# CONN.net
KiCad netlist of a schematic drawn in Altium Designer
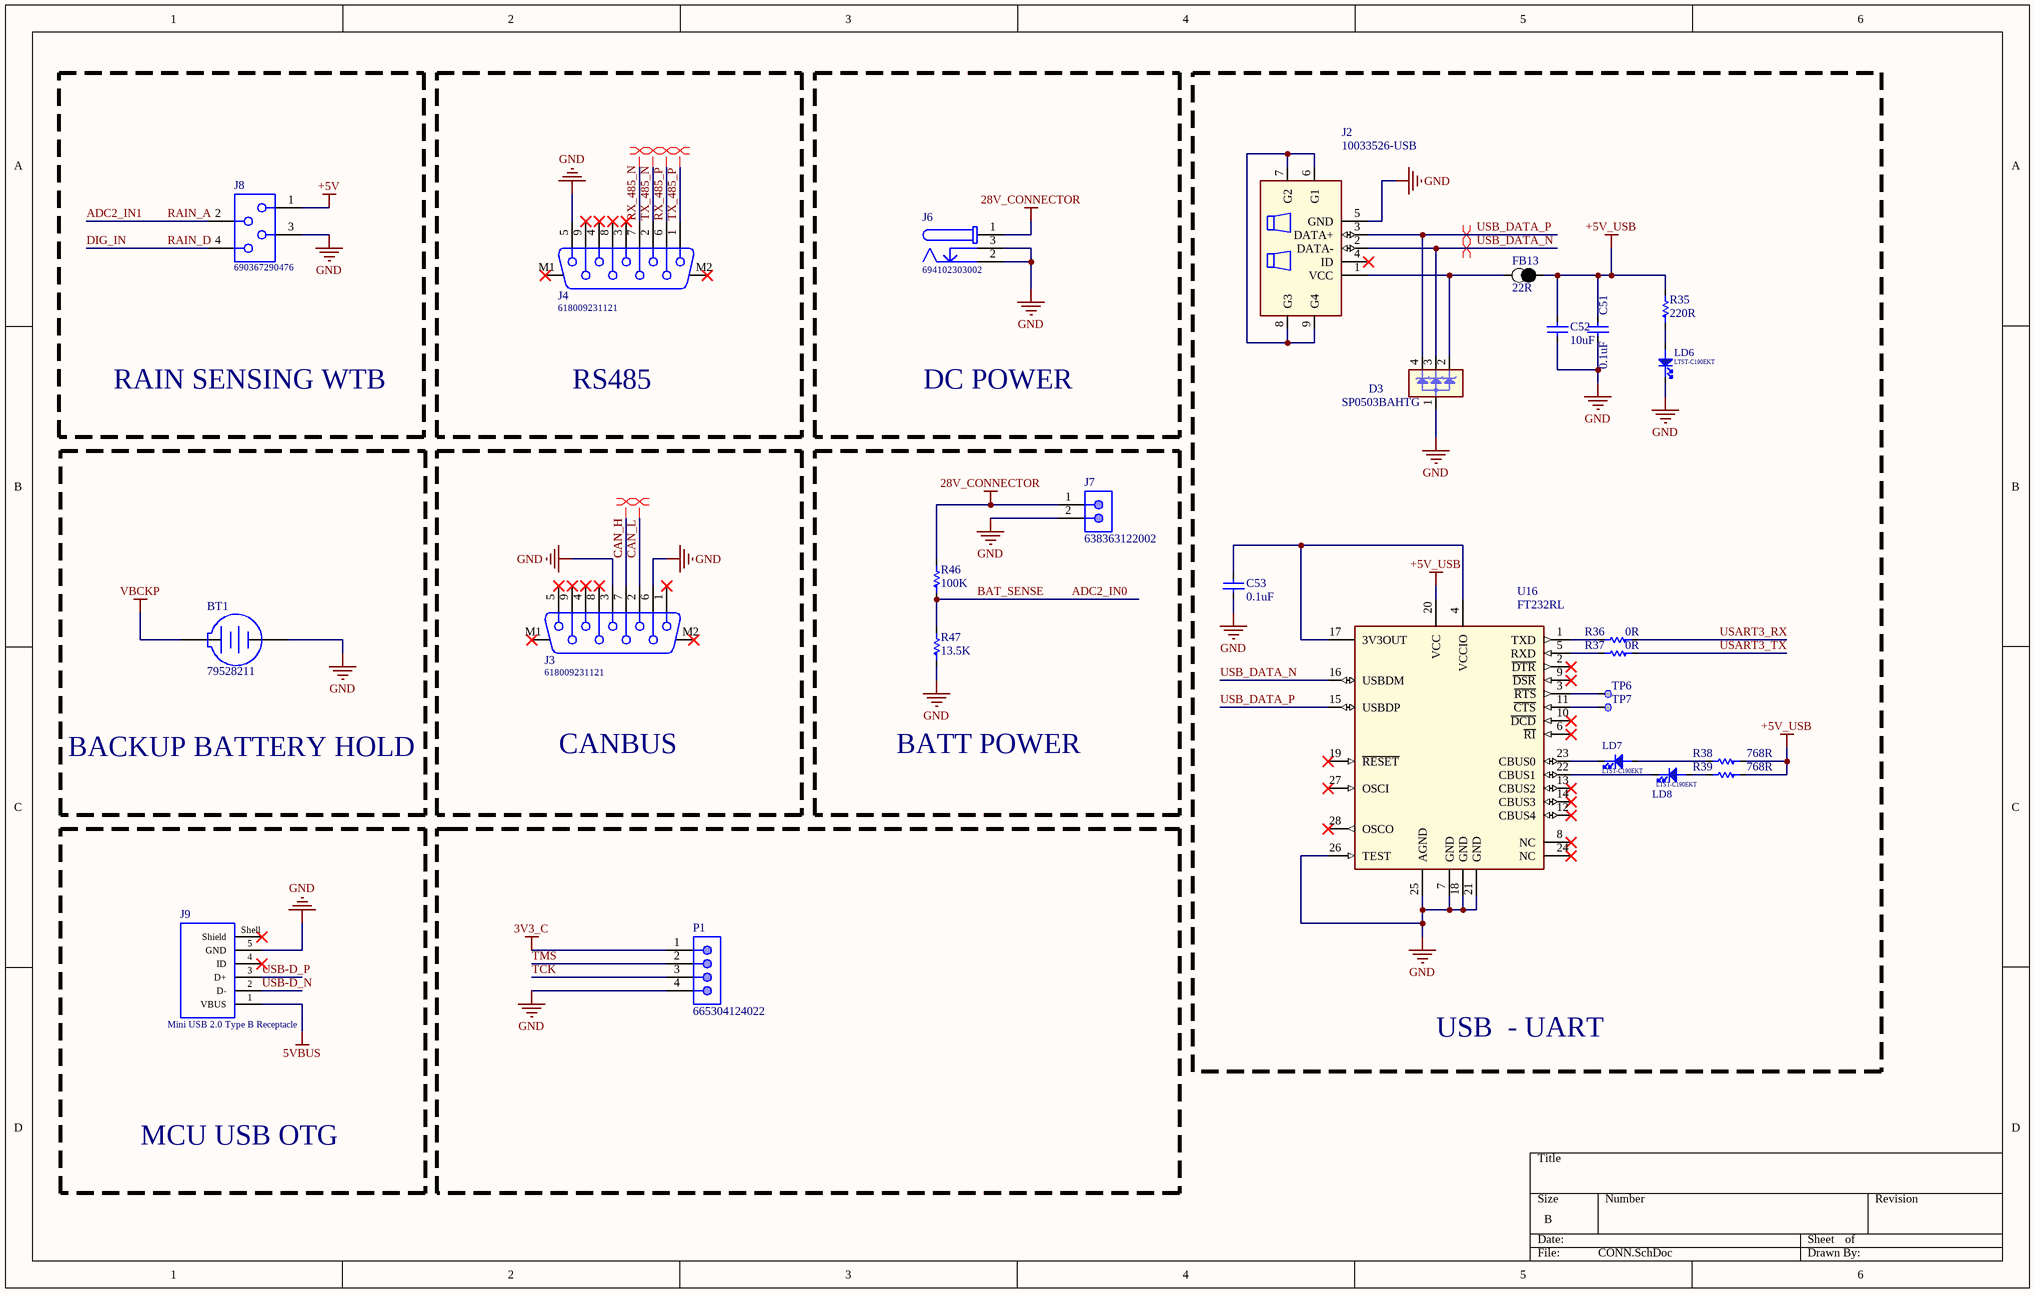
[diagram p0: CONN.SchDoc]

(export (version "E")
  (design (tool "Eeschema 10.0.6"))
  (components
    (comp (ref "BT1")
      (value "79528211")
      (footprint "79528211")
      (description "WA-BCPH Battery Holder, THT, Battery Type 2025/2032")
      (fields (field (name "MANUFACTURER") "Wurth Elektronik"))
      (libsource (lib "Altium_WA-BCPH (rev21a)") (part "79528211"))
    )
    (comp (ref "C51")
      (value "0.1uF")
      (footprint "CAPC1608-0603X85N")
      (description "CAP CER 0.1UF 25V X7R 0603")
      (fields (field (name "MANUFACTURER") "Yageo") (field (name "VOLTAGE") "25V"))
      (libsource (lib "capacitor") (part "Capacitor Ceramic"))
    )
    (comp (ref "C52")
      (value "10uF")
      (footprint "CAPC3216-1206X100N")
      (description "CAP CER 10UF 16V X7R 1206")
      (fields (field (name "MANUFACTURER") "TDK Corporation") (field (name "VOLTAGE") "16V"))
      (libsource (lib "capacitor") (part "Capacitor Ceramic"))
    )
    (comp (ref "C53")
      (value "0.1uF")
      (footprint "CAPC1608-0603X85N")
      (description "CAP CER 0.1UF 25V X7R 0603")
      (fields (field (name "MANUFACTURER") "Yageo") (field (name "VOLTAGE") "25V"))
      (libsource (lib "capacitor") (part "Capacitor Ceramic"))
    )
    (comp (ref "D3")
      (value "SP0503BAHTG")
      (footprint "SOT143N")
      (description "30pF 30kV Unidirectional TVS Array, SP05 Series")
      (fields (field (name "MANUFACTURER") "LittelFuse") (field (name "VOLTAGE") "up to : 30kV"))
      (libsource (lib "diode") (part "SP0503BAHTG"))
    )
    (comp (ref "FB13")
      (value "22R")
      (footprint "INDC2012-0805X90N")
      (description "FERRITE BEAD 22 OHM 0805 1LN")
      (fields (field (name "MANUFACTURER") "Murata") (field (name "VOLTAGE") "0.8A"))
      (libsource (lib "Inductors & Transformers") (part "Inductor EMI suppresion"))
    )
    (comp (ref "J2")
      (value "10033526-USB")
      (footprint "USB/SM0.8-6H5")
      (description "CONN MINI USB RCPT RA TYPE B SMD")
      (fields (field (name "MANUFACTURER") "Amphenol") (field (name "TOLERANCE") "1A"))
      (libsource (lib "connectors_Schlib") (part "10033526-USB"))
    )
    (comp (ref "J3")
      (value "618009231121")
      (footprint "618009231121")
      (description "WR-DSUB 8.08mm Female PCB Connector with Hex Screw, Angled, 9p")
      (fields (field (name "MANUFACTURER") "Wurth Elektronik"))
      (libsource (lib "Altium_WR-DSUB (rev21a)") (part "618009231121"))
    )
    (comp (ref "J4")
      (value "618009231121")
      (footprint "618009231121")
      (description "WR-DSUB 8.08mm Female PCB Connector with Hex Screw, Angled, 9p")
      (fields (field (name "MANUFACTURER") "Wurth Elektronik"))
      (libsource (lib "Altium_WR-DSUB (rev21a)") (part "618009231121"))
    )
    (comp (ref "J6")
      (value "694102303002")
      (footprint "694102303002")
      (description "WR-DC DC Power Jack Connector, Male, Right Angled, 30V, 2A")
      (fields (field (name "MANUFACTURER") "Wurth Elektronik"))
      (libsource (lib "Altium_WR-DC (rev21b)") (part "694102303002"))
    )
    (comp (ref "J7")
      (value "638363122002")
      (footprint "638363122002")
      (description "WR-FAST THT Male Header Angled Blade, pitch 7.62mm, 2p")
      (fields (field (name "PUBLISHER") "Wurth Elektronik"))
      (libsource (lib "Altium_WR-FAST (rev19a)") (part "638363122002"))
    )
    (comp (ref "J8")
      (value "690367290476")
      (footprint "690367290476")
      (description "WR-MM Mini Module Connector, Female, SMT, with Latch & Polarization, Straight, 4p")
      (fields (field (name "MANUFACTURER") "Wurth Elektronik"))
      (libsource (lib "Altium_WR-MM (rev21b)") (part "690367290476"))
    )
    (comp (ref "J9")
      (value "Mini USB 2.0 Type B Receptacle")
      (footprint "614105150721")
      (description "Mini USB 2.0 Type B, Receptacle, Vertical, THT")
      (fields
        (field (name "MANUFACTURER") "Wurth Elektronik")
        (field (name "MANUFACTURER PART NUMBER") "614105150721")
      )
      (libsource (lib "Altium_WR-USB (rev21b)") (part "614105150721"))
    )
    (comp (ref "LD6")
      (value "LTST-C190EKT")
      (footprint "LED0603-1608X55N-RED")
      (description "LED RED CLEAR CHIP SMD")
      (fields (field (name "MANUFACTURER") "Lite-On Inc") (field (name "VOLTAGE") "2V"))
      (libsource (lib "diode") (part "LED-0603"))
    )
    (comp (ref "LD7")
      (value "LTST-C190EKT")
      (footprint "LED0603-1608X55N-RED")
      (description "LED RED CLEAR CHIP SMD")
      (fields (field (name "MANUFACTURER") "Lite-On Inc") (field (name "VOLTAGE") "2V"))
      (libsource (lib "diode") (part "LED-0603"))
    )
    (comp (ref "LD8")
      (value "LTST-C190EKT")
      (footprint "LED0603-1608X55N-RED")
      (description "LED RED CLEAR CHIP SMD")
      (fields (field (name "MANUFACTURER") "Lite-On Inc") (field (name "VOLTAGE") "2V"))
      (libsource (lib "diode") (part "LED-0603"))
    )
    (comp (ref "P1")
      (value "665304124022")
      (footprint "665304124022")
      (description "WR-WTB SMT Male Vertical Shrouded Header, pitch 1mm, 4p")
      (fields (field (name "PUBLISHER") "Wurth Elektronik"))
      (libsource (lib "Altium_WR-WTB (rev20a)") (part "665304124022"))
    )
    (comp (ref "R35")
      (value "220R")
      (footprint "RESC1608-0603X50N")
      (description "RES SMD 220 OHM 5% 1/10W 0603")
      (fields (field (name "MANUFACTURER") "Yageo") (field (name "TOLERANCE") "%1"))
      (libsource (lib "resistor") (part "Resistor SMD"))
    )
    (comp (ref "R36")
      (value "0R")
      (footprint "RESC1608-0603X50N")
      (description "RES SMD 0 OHM JUMPER 1/10W 0603")
      (fields (field (name "MANUFACTURER") "Yageo") (field (name "TOLERANCE") "±1%"))
      (libsource (lib "resistor") (part "Resistor SMD"))
    )
    (comp (ref "R37")
      (value "0R")
      (footprint "RESC1608-0603X50N")
      (description "RES SMD 0 OHM JUMPER 1/10W 0603")
      (fields (field (name "MANUFACTURER") "Yageo") (field (name "TOLERANCE") "±1%"))
      (libsource (lib "resistor") (part "Resistor SMD"))
    )
    (comp (ref "R38")
      (value "768R")
      (footprint "RESC2012-0805X50N")
      (description "RES SMD 768 OHM 1% 1/8W 0805")
      (fields (field (name "MANUFACTURER") "YAGEO") (field (name "TOLERANCE") "±1%"))
      (libsource (lib "resistor") (part "Resistor SMD"))
    )
    (comp (ref "R39")
      (value "768R")
      (footprint "RESC2012-0805X50N")
      (description "RES SMD 768 OHM 1% 1/8W 0805")
      (fields (field (name "MANUFACTURER") "YAGEO") (field (name "TOLERANCE") "±1%"))
      (libsource (lib "resistor") (part "Resistor SMD"))
    )
    (comp (ref "R46")
      (value "100K")
      (footprint "RESC1608-0603X50N")
      (description "RES SMD 10K OHM 1% 1/10W 0603")
      (fields (field (name "MANUFACTURER") "Yageo"))
      (libsource (lib "ANTSIS_PASSIVE") (part "RESISTOR 10K"))
    )
    (comp (ref "R47")
      (value "13.5K")
      (footprint "RESC1608-0603X50N")
      (description "RES SMD 10K OHM 1% 1/10W 0603")
      (fields (field (name "MANUFACTURER") "Yageo"))
      (libsource (lib "ANTSIS_PASSIVE") (part "RESISTOR 10K"))
    )
    (comp (ref "TP6")
      (value "TP")
      (footprint "TP-ROUND")
      (description "Test point")
      (libsource (lib "others") (part "TP"))
    )
    (comp (ref "TP7")
      (value "TP")
      (footprint "TP-ROUND")
      (description "Test point")
      (libsource (lib "others") (part "TP"))
    )
    (comp (ref "U16")
      (value "FT232RL")
      (footprint "SSOP65P790-28N")
      (description "USB FS SERIAL UART")
      (fields (field (name "MANUFACTURER") "FTDI") (field (name "TOLERANCE") "-40 to +85C"))
      (libsource (lib "ctech") (part "FT232RL"))
    )
  )
  (nets
    (net (code "1") (name "+5V") (class "Default")
      (node (ref "J8") (pin "1") (pinfunction "1_1") (pintype "passive"))
    )
    (net (code "2") (name "+5V_USB") (class "Default")
      (node (ref "C51") (pin "1") (pinfunction "1_1") (pintype "passive"))
      (node (ref "C52") (pin "2") (pinfunction "2_2") (pintype "passive"))
      (node (ref "FB13") (pin "1") (pinfunction "1_1") (pintype "passive"))
      (node (ref "R35") (pin "2") (pinfunction "2_2") (pintype "passive"))
      (node (ref "R38") (pin "1") (pinfunction "1_1") (pintype "passive"))
      (node (ref "R39") (pin "1") (pinfunction "1_1") (pintype "passive"))
      (node (ref "U16") (pin "20") (pinfunction "VCC_20") (pintype "power_in"))
    )
    (net (code "3") (name "/ADC2_IN0") (class "Default")
      (node (ref "R46") (pin "1") (pinfunction "1_1") (pintype "passive"))
      (node (ref "R47") (pin "2") (pinfunction "2_2") (pintype "passive"))
    )
    (net (code "4") (name "/ADC2_IN1") (class "Default")
      (node (ref "J8") (pin "2") (pinfunction "2_2") (pintype "passive"))
    )
    (net (code "5") (name "/CAN_H") (class "Default")
      (node (ref "J3") (pin "7") (pinfunction "7_7") (pintype "passive"))
    )
    (net (code "6") (name "/CAN_L") (class "Default")
      (node (ref "J3") (pin "2") (pinfunction "2_2") (pintype "passive"))
    )
    (net (code "7") (name "/DIG_IN") (class "Default")
      (node (ref "J8") (pin "4") (pinfunction "4_4") (pintype "passive"))
    )
    (net (code "8") (name "/RX_485_N") (class "Default")
      (node (ref "J4") (pin "7") (pinfunction "7_7") (pintype "passive"))
    )
    (net (code "9") (name "/RX_485_P") (class "Default")
      (node (ref "J4") (pin "6") (pinfunction "6_6") (pintype "passive"))
    )
    (net (code "10") (name "/TCK") (class "Default")
      (node (ref "P1") (pin "3") (pinfunction "3_3") (pintype "passive"))
    )
    (net (code "11") (name "/TMS") (class "Default")
      (node (ref "P1") (pin "2") (pinfunction "2_2") (pintype "passive"))
    )
    (net (code "12") (name "/TX_485_N") (class "Default")
      (node (ref "J4") (pin "2") (pinfunction "2_2") (pintype "passive"))
    )
    (net (code "13") (name "/TX_485_P") (class "Default")
      (node (ref "J4") (pin "1") (pinfunction "1_1") (pintype "passive"))
    )
    (net (code "14") (name "/USART3_RX") (class "Default")
      (node (ref "R36") (pin "1") (pinfunction "1_1") (pintype "passive"))
    )
    (net (code "15") (name "/USART3_TX") (class "Default")
      (node (ref "R37") (pin "1") (pinfunction "1_1") (pintype "passive"))
    )
    (net (code "16") (name "/USB-D_N") (class "Default")
      (node (ref "J9") (pin "2") (pinfunction "D-_2") (pintype "passive"))
    )
    (net (code "17") (name "/USB-D_P") (class "Default")
      (node (ref "J9") (pin "3") (pinfunction "D+_3") (pintype "passive"))
    )
    (net (code "18") (name "/USB_DATA_N") (class "Default")
      (node (ref "D3") (pin "3") (pinfunction "C2_3") (pintype "passive"))
      (node (ref "J2") (pin "2") (pinfunction "DATA-_2") (pintype "bidirectional"))
      (node (ref "U16") (pin "16") (pinfunction "USBDM_16") (pintype "bidirectional"))
    )
    (net (code "19") (name "/USB_DATA_P") (class "Default")
      (node (ref "D3") (pin "4") (pinfunction "C1_4") (pintype "passive"))
      (node (ref "J2") (pin "3") (pinfunction "DATA+_3") (pintype "bidirectional"))
      (node (ref "U16") (pin "15") (pinfunction "USBDP_15") (pintype "bidirectional"))
    )
    (net (code "20") (name "3V3_C") (class "Default")
      (node (ref "P1") (pin "1") (pinfunction "1_1") (pintype "passive"))
    )
    (net (code "21") (name "5VBUS") (class "Default")
      (node (ref "J9") (pin "1") (pinfunction "VBUS_1") (pintype "passive"))
    )
    (net (code "22") (name "28V_CONNECTOR") (class "Default")
      (node (ref "J6") (pin "1") (pinfunction "1_1") (pintype "passive"))
      (node (ref "J7") (pin "1") (pinfunction "1_1") (pintype "passive"))
      (node (ref "R46") (pin "2") (pinfunction "2_2") (pintype "passive"))
    )
    (net (code "23") (name "GND") (class "Default")
      (node (ref "BT1") (pin "2") (pinfunction "-_2") (pintype "passive"))
      (node (ref "C51") (pin "2") (pinfunction "2_2") (pintype "passive"))
      (node (ref "C52") (pin "1") (pinfunction "1_1") (pintype "passive"))
      (node (ref "C53") (pin "2") (pinfunction "2_2") (pintype "passive"))
      (node (ref "D3") (pin "1") (pinfunction "A_1") (pintype "passive"))
      (node (ref "J2") (pin "5") (pinfunction "GND_5") (pintype "power_in"))
      (node (ref "J3") (pin "3") (pinfunction "3_3") (pintype "passive"))
      (node (ref "J3") (pin "6") (pinfunction "6_6") (pintype "passive"))
      (node (ref "J4") (pin "5") (pinfunction "5_5") (pintype "passive"))
      (node (ref "J6") (pin "2") (pinfunction "2_2") (pintype "passive"))
      (node (ref "J6") (pin "3") (pinfunction "3_3") (pintype "passive"))
      (node (ref "J7") (pin "2") (pinfunction "2_2") (pintype "passive"))
      (node (ref "J8") (pin "3") (pinfunction "3_3") (pintype "passive"))
      (node (ref "J9") (pin "5") (pinfunction "GND_5") (pintype "passive"))
      (node (ref "LD6") (pin "2") (pinfunction "2_2") (pintype "passive"))
      (node (ref "P1") (pin "4") (pinfunction "4_4") (pintype "passive"))
      (node (ref "R47") (pin "1") (pinfunction "1_1") (pintype "passive"))
      (node (ref "U16") (pin "18") (pinfunction "GND_18") (pintype "power_in"))
      (node (ref "U16") (pin "21") (pinfunction "GND_21") (pintype "power_in"))
      (node (ref "U16") (pin "25") (pinfunction "AGND_25") (pintype "power_in"))
      (node (ref "U16") (pin "26") (pinfunction "TEST_26") (pintype "input"))
      (node (ref "U16") (pin "7") (pinfunction "GND_7") (pintype "power_in"))
    )
    (net (code "24") (name "Net-(D3-C3)") (class "Default")
      (node (ref "D3") (pin "2") (pinfunction "C3_2") (pintype "passive"))
      (node (ref "FB13") (pin "2") (pinfunction "2_2") (pintype "passive"))
      (node (ref "J2") (pin "1") (pinfunction "VCC_1") (pintype "power_in"))
    )
    (net (code "25") (name "Net-(J2-G1)") (class "Default")
      (node (ref "J2") (pin "6") (pinfunction "G1_6") (pintype "power_in"))
      (node (ref "J2") (pin "7") (pinfunction "G2_7") (pintype "power_in"))
      (node (ref "J2") (pin "8") (pinfunction "G3_8") (pintype "power_in"))
      (node (ref "J2") (pin "9") (pinfunction "G4_9") (pintype "power_in"))
    )
    (net (code "26") (name "Net-(LD6-Pad1)") (class "Default")
      (node (ref "LD6") (pin "1") (pinfunction "1_1") (pintype "passive"))
      (node (ref "R35") (pin "1") (pinfunction "1_1") (pintype "passive"))
    )
    (net (code "27") (name "Net-(LD7-Pad1)") (class "Default")
      (node (ref "LD7") (pin "1") (pinfunction "1_1") (pintype "passive"))
      (node (ref "R38") (pin "2") (pinfunction "2_2") (pintype "passive"))
    )
    (net (code "28") (name "Net-(LD8-Pad1)") (class "Default")
      (node (ref "LD8") (pin "1") (pinfunction "1_1") (pintype "passive"))
      (node (ref "R39") (pin "2") (pinfunction "2_2") (pintype "passive"))
    )
    (net (code "29") (name "Net-(U16-3V3OUT)") (class "Default")
      (node (ref "C53") (pin "1") (pinfunction "1_1") (pintype "passive"))
      (node (ref "U16") (pin "17") (pinfunction "3V3OUT_17") (pintype "passive"))
      (node (ref "U16") (pin "4") (pinfunction "VCCIO_4") (pintype "power_in"))
    )
    (net (code "30") (name "Net-(U16-CBUS0)") (class "Default")
      (node (ref "LD7") (pin "2") (pinfunction "2_2") (pintype "passive"))
      (node (ref "U16") (pin "23") (pinfunction "CBUS0_23") (pintype "bidirectional"))
    )
    (net (code "31") (name "Net-(U16-CBUS1)") (class "Default")
      (node (ref "LD8") (pin "2") (pinfunction "2_2") (pintype "passive"))
      (node (ref "U16") (pin "22") (pinfunction "CBUS1_22") (pintype "bidirectional"))
    )
    (net (code "32") (name "Net-(U16-RXD)") (class "Default")
      (node (ref "R37") (pin "2") (pinfunction "2_2") (pintype "passive"))
      (node (ref "U16") (pin "5") (pinfunction "RXD_5") (pintype "input"))
    )
    (net (code "33") (name "Net-(U16-TXD)") (class "Default")
      (node (ref "R36") (pin "2") (pinfunction "2_2") (pintype "passive"))
      (node (ref "U16") (pin "1") (pinfunction "TXD_1") (pintype "output"))
    )
    (net (code "34") (name "Net-(U16-~{CTS})") (class "Default")
      (node (ref "TP7") (pin "1") (pinfunction "1_1") (pintype "passive"))
      (node (ref "U16") (pin "11") (pinfunction "~{CTS}_11") (pintype "input"))
    )
    (net (code "35") (name "Net-(U16-~{RTS})") (class "Default")
      (node (ref "TP6") (pin "1") (pinfunction "1_1") (pintype "passive"))
      (node (ref "U16") (pin "3") (pinfunction "~{RTS}_3") (pintype "output"))
    )
    (net (code "36") (name "VBCKP") (class "Default")
      (node (ref "BT1") (pin "1") (pinfunction "+_1") (pintype "passive"))
    )
    (net (code "37") (name "unconnected-(J2-ID-Pad4)") (class "Default")
      (node (ref "J2") (pin "4") (pinfunction "ID_4") (pintype "passive+no_connect"))
    )
    (net (code "38") (name "unconnected-(J3-Pad1)") (class "Default")
      (node (ref "J3") (pin "1") (pinfunction "1_1") (pintype "passive+no_connect"))
    )
    (net (code "39") (name "unconnected-(J3-Pad4)") (class "Default")
      (node (ref "J3") (pin "4") (pinfunction "4_4") (pintype "passive+no_connect"))
    )
    (net (code "40") (name "unconnected-(J3-Pad5)") (class "Default")
      (node (ref "J3") (pin "5") (pinfunction "5_5") (pintype "passive+no_connect"))
    )
    (net (code "41") (name "unconnected-(J3-Pad8)") (class "Default")
      (node (ref "J3") (pin "8") (pinfunction "8_8") (pintype "passive+no_connect"))
    )
    (net (code "42") (name "unconnected-(J3-Pad9)") (class "Default")
      (node (ref "J3") (pin "9") (pinfunction "9_9") (pintype "passive+no_connect"))
    )
    (net (code "43") (name "unconnected-(J3-PadM1)") (class "Default")
      (node (ref "J3") (pin "M1") (pinfunction "M1_M1") (pintype "passive+no_connect"))
    )
    (net (code "44") (name "unconnected-(J3-PadM2)") (class "Default")
      (node (ref "J3") (pin "M2") (pinfunction "M2_M2") (pintype "passive+no_connect"))
    )
    (net (code "45") (name "unconnected-(J4-Pad3)") (class "Default")
      (node (ref "J4") (pin "3") (pinfunction "3_3") (pintype "passive+no_connect"))
    )
    (net (code "46") (name "unconnected-(J4-Pad4)") (class "Default")
      (node (ref "J4") (pin "4") (pinfunction "4_4") (pintype "passive+no_connect"))
    )
    (net (code "47") (name "unconnected-(J4-Pad8)") (class "Default")
      (node (ref "J4") (pin "8") (pinfunction "8_8") (pintype "passive+no_connect"))
    )
    (net (code "48") (name "unconnected-(J4-Pad9)") (class "Default")
      (node (ref "J4") (pin "9") (pinfunction "9_9") (pintype "passive+no_connect"))
    )
    (net (code "49") (name "unconnected-(J4-PadM1)") (class "Default")
      (node (ref "J4") (pin "M1") (pinfunction "M1_M1") (pintype "passive+no_connect"))
    )
    (net (code "50") (name "unconnected-(J4-PadM2)") (class "Default")
      (node (ref "J4") (pin "M2") (pinfunction "M2_M2") (pintype "passive+no_connect"))
    )
    (net (code "51") (name "unconnected-(J9-ID-Pad4)") (class "Default")
      (node (ref "J9") (pin "4") (pinfunction "ID_4") (pintype "passive+no_connect"))
    )
    (net (code "52") (name "unconnected-(J9-Shield-PadShell)") (class "Default")
      (node (ref "J9") (pin "Shell") (pinfunction "Shield_Shell") (pintype "passive+no_connect"))
    )
    (net (code "53") (name "unconnected-(U16-CBUS2-Pad13)") (class "Default")
      (node (ref "U16") (pin "13") (pinfunction "CBUS2_13") (pintype "bidirectional+no_connect"))
    )
    (net (code "54") (name "unconnected-(U16-CBUS3-Pad14)") (class "Default")
      (node (ref "U16") (pin "14") (pinfunction "CBUS3_14") (pintype "bidirectional+no_connect"))
    )
    (net (code "55") (name "unconnected-(U16-CBUS4-Pad12)") (class "Default")
      (node (ref "U16") (pin "12") (pinfunction "CBUS4_12") (pintype "bidirectional+no_connect"))
    )
    (net (code "56") (name "unconnected-(U16-NC-Pad8)") (class "Default")
      (node (ref "U16") (pin "8") (pinfunction "NC_8") (pintype "passive+no_connect"))
    )
    (net (code "57") (name "unconnected-(U16-NC-Pad24)") (class "Default")
      (node (ref "U16") (pin "24") (pinfunction "NC_24") (pintype "passive+no_connect"))
    )
    (net (code "58") (name "unconnected-(U16-OSCI-Pad27)") (class "Default")
      (node (ref "U16") (pin "27") (pinfunction "OSCI_27") (pintype "input+no_connect"))
    )
    (net (code "59") (name "unconnected-(U16-OSCO-Pad28)") (class "Default")
      (node (ref "U16") (pin "28") (pinfunction "OSCO_28") (pintype "output+no_connect"))
    )
    (net (code "60") (name "unconnected-(U16-~{DCD}-Pad10)") (class "Default")
      (node (ref "U16") (pin "10") (pinfunction "~{DCD}_10") (pintype "input+no_connect"))
    )
    (net (code "61") (name "unconnected-(U16-~{DSR}-Pad9)") (class "Default")
      (node (ref "U16") (pin "9") (pinfunction "~{DSR}_9") (pintype "input+no_connect"))
    )
    (net (code "62") (name "unconnected-(U16-~{DTR}-Pad2)") (class "Default")
      (node (ref "U16") (pin "2") (pinfunction "~{DTR}_2") (pintype "output+no_connect"))
    )
    (net (code "63") (name "unconnected-(U16-~{RESET}-Pad19)") (class "Default")
      (node (ref "U16") (pin "19") (pinfunction "~{RESET}_19") (pintype "input+no_connect"))
    )
    (net (code "64") (name "unconnected-(U16-~{RI}-Pad6)") (class "Default")
      (node (ref "U16") (pin "6") (pinfunction "~{RI}_6") (pintype "input+no_connect"))
    )
  )
)
